# SparkFun_Thing_Plus_NORA_W306.net
KiCad netlist of a schematic drawn in EAGLE
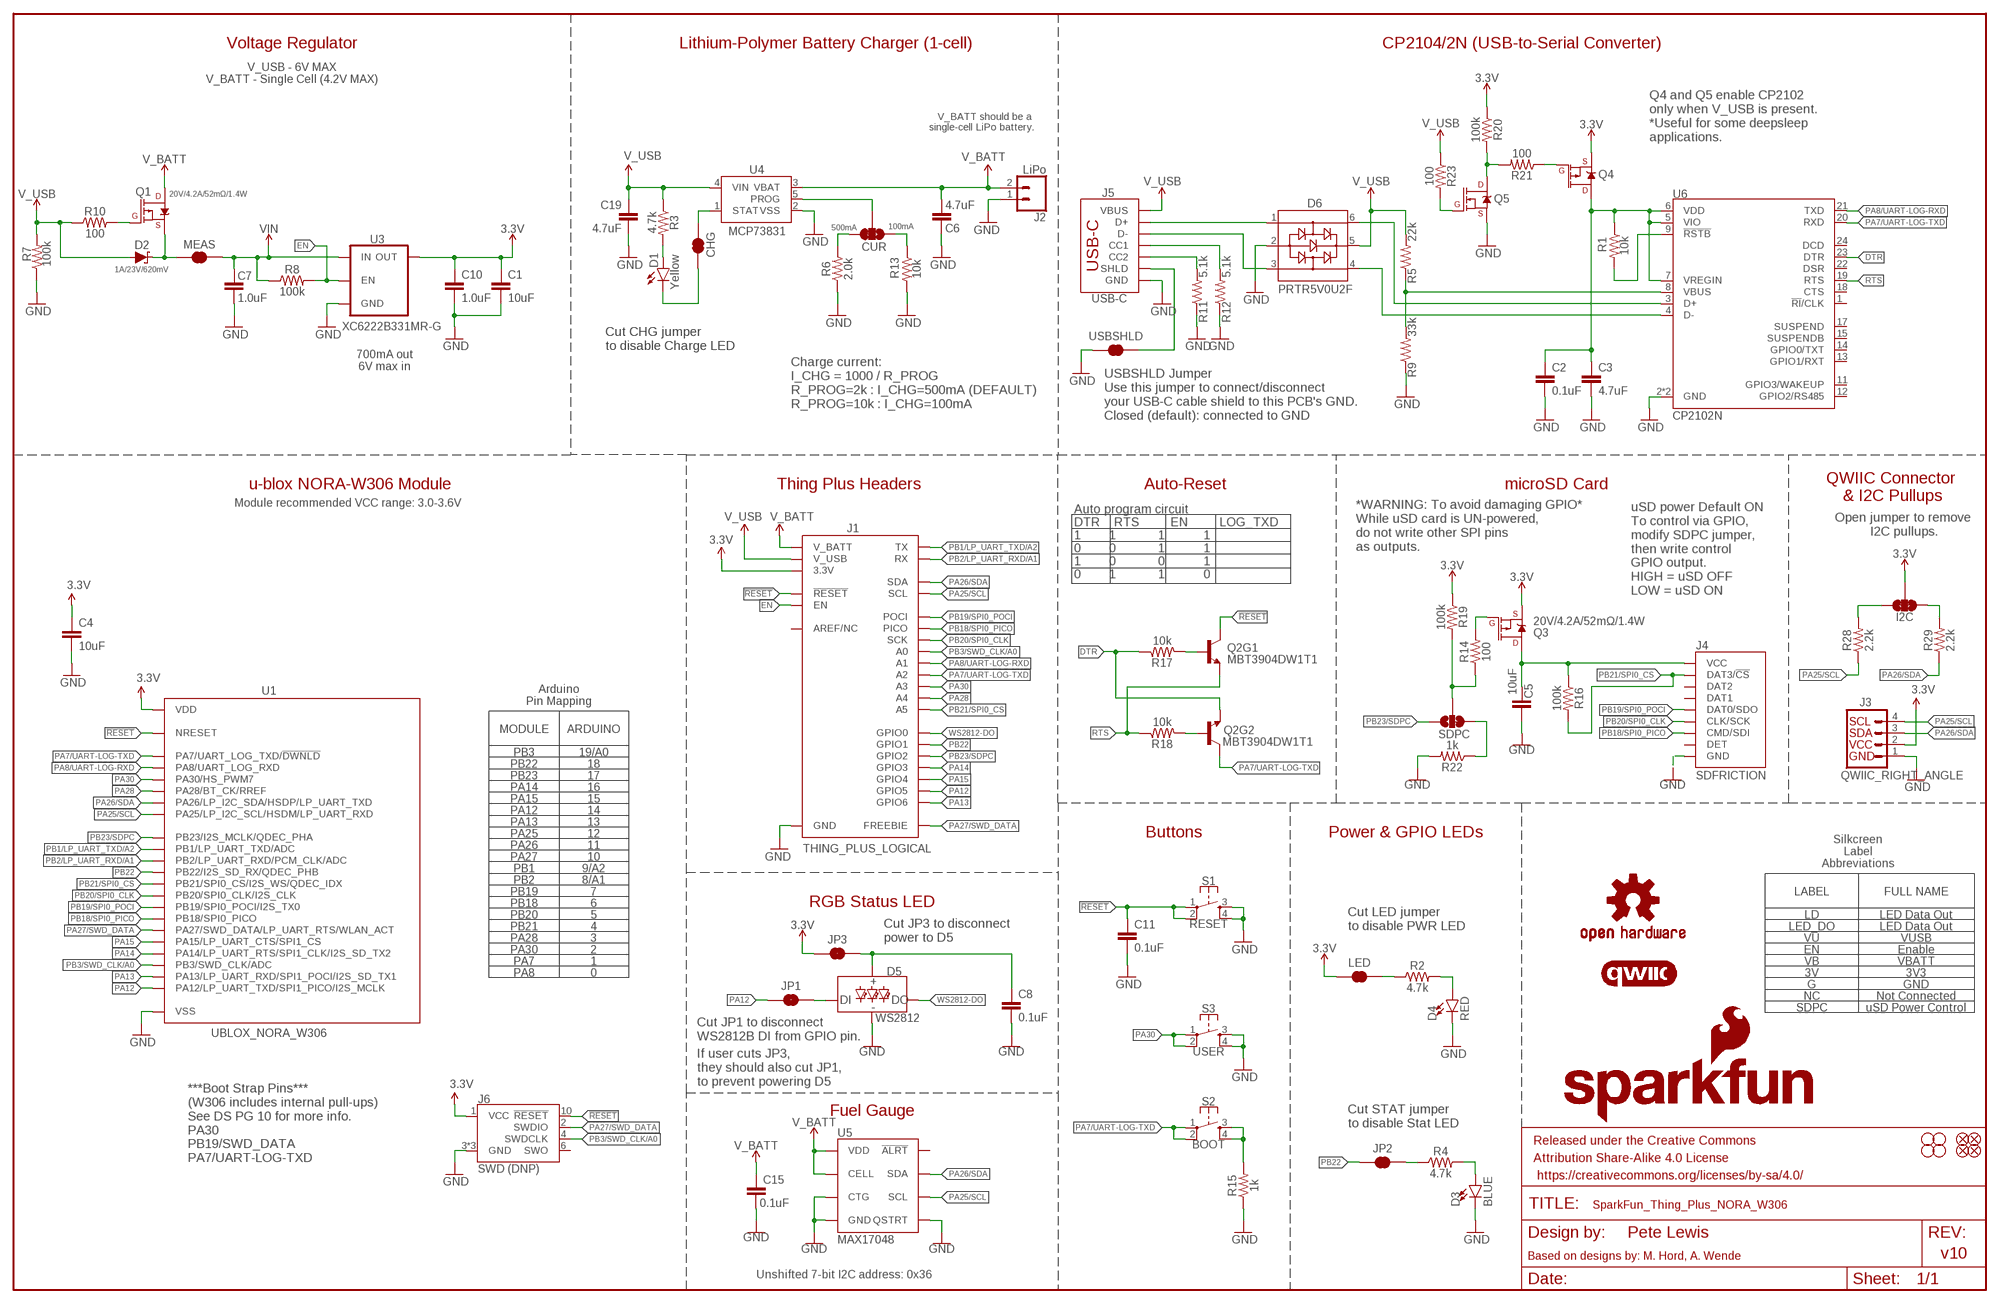
[diagram p0: schematic, sheet 1]

(export (version "E")
  (design (tool "Eeschema 10.0.6"))
  (components
    (comp (ref "C1")
      (value "10uF")
      (footprint "eagle-import:0402-TIGHT")
      (libsource (lib "eagle-import") (part "10UF-0402T-6.3V-20%"))
    )
    (comp (ref "C2")
      (value "0.1uF")
      (footprint "eagle-import:0402-TIGHT")
      (libsource (lib "eagle-import") (part "0.1UF-0402T-16V-10%"))
    )
    (comp (ref "C3")
      (value "4.7uF")
      (footprint "eagle-import:0603")
      (libsource (lib "eagle-import") (part "4.7UF-0603-35V-(20%)"))
    )
    (comp (ref "C4")
      (value "10uF")
      (footprint "eagle-import:0402-TIGHT")
      (libsource (lib "eagle-import") (part "10UF-0402T-6.3V-20%"))
    )
    (comp (ref "C5")
      (value "10uF")
      (footprint "eagle-import:0402-TIGHT")
      (libsource (lib "eagle-import") (part "10UF-0402T-6.3V-20%"))
    )
    (comp (ref "C6")
      (value "4.7uF")
      (footprint "eagle-import:0603")
      (libsource (lib "eagle-import") (part "4.7UF-0603-35V-(20%)"))
    )
    (comp (ref "C7")
      (value "1.0uF")
      (footprint "eagle-import:0402-TIGHT")
      (libsource (lib "eagle-import") (part "1.0UF-0402T-16V-10%"))
    )
    (comp (ref "C8")
      (value "0.1uF")
      (footprint "eagle-import:0402-TIGHT")
      (libsource (lib "eagle-import") (part "0.1UF-0402T-16V-10%"))
    )
    (comp (ref "C10")
      (value "1.0uF")
      (footprint "eagle-import:0402-TIGHT")
      (libsource (lib "eagle-import") (part "1.0UF-0402T-16V-10%"))
    )
    (comp (ref "C11")
      (value "0.1uF")
      (footprint "eagle-import:0402-TIGHT")
      (libsource (lib "eagle-import") (part "0.1UF-0402T-16V-10%"))
    )
    (comp (ref "C15")
      (value "0.1uF")
      (footprint "eagle-import:0402-TIGHT")
      (libsource (lib "eagle-import") (part "0.1UF-0402T-16V-10%"))
    )
    (comp (ref "C19")
      (value "4.7uF")
      (footprint "eagle-import:0603")
      (libsource (lib "eagle-import") (part "4.7UF-0603-35V-(20%)"))
    )
    (comp (ref "CHG")
      (value "JUMPER-SMT_2_NC_TRACE_SILK")
      (footprint "eagle-import:SMT-JUMPER_2_NC_TRACE_SILK")
      (libsource (lib "eagle-import") (part "JUMPER-SMT_2_NC_TRACE_SILK"))
    )
    (comp (ref "CUR")
      (value "JUMPER-SMT_3_1-NC_TRACE_SILK")
      (footprint "eagle-import:SMT-JUMPER_3_1-NC_TRACE_SILK")
      (libsource (lib "eagle-import") (part "JUMPER-SMT_3_1-NC_TRACE_SILK"))
    )
    (comp (ref "D1")
      (value "Yellow")
      (footprint "eagle-import:LED-0603")
      (libsource (lib "eagle-import") (part "LED-YELLOW0603"))
    )
    (comp (ref "D2")
      (value "1A/23V/620mV")
      (footprint "eagle-import:SOD-323")
      (libsource (lib "eagle-import") (part "DIODE-SCHOTTKY-BAT20J"))
    )
    (comp (ref "D3")
      (value "BLUE")
      (footprint "eagle-import:LED-0603")
      (libsource (lib "eagle-import") (part "LED-BLUE0603"))
    )
    (comp (ref "D4")
      (value "RED")
      (footprint "eagle-import:LED-0603")
      (libsource (lib "eagle-import") (part "LED-RED_0603-KB"))
    )
    (comp (ref "D5")
      (value "WS2812")
      (footprint "eagle-import:WS2812-2020")
      (libsource (lib "eagle-import") (part "WS2812_2020"))
    )
    (comp (ref "D6")
      (value "PRTR5V0U2F")
      (footprint "eagle-import:SOT886")
      (libsource (lib "eagle-import") (part "PRTR5V0U2F"))
    )
    (comp (ref "FD1")
      (value "FIDUCIALUFIDUCIAL")
      (footprint "eagle-import:FIDUCIAL-MICRO")
      (libsource (lib "eagle-import") (part "FIDUCIALUFIDUCIAL"))
    )
    (comp (ref "FD2")
      (value "FIDUCIALUFIDUCIAL")
      (footprint "eagle-import:FIDUCIAL-MICRO")
      (libsource (lib "eagle-import") (part "FIDUCIALUFIDUCIAL"))
    )
    (comp (ref "FD3")
      (value "FIDUCIALUFIDUCIAL")
      (footprint "eagle-import:FIDUCIAL-MICRO")
      (libsource (lib "eagle-import") (part "FIDUCIALUFIDUCIAL"))
    )
    (comp (ref "FD4")
      (value "FIDUCIALUFIDUCIAL")
      (footprint "eagle-import:FIDUCIAL-MICRO")
      (libsource (lib "eagle-import") (part "FIDUCIALUFIDUCIAL"))
    )
    (comp (ref "FRAME1")
      (value "FRAME-LEDGER")
      (footprint "eagle-import:CREATIVE_COMMONS")
      (libsource (lib "eagle-import") (part "FRAME-LEDGER"))
    )
    (comp (ref "H1")
      (value "STAND-OFF")
      (footprint "eagle-import:STAND-OFF")
      (libsource (lib "eagle-import") (part "STAND-OFF"))
    )
    (comp (ref "H2")
      (value "STAND-OFF")
      (footprint "eagle-import:STAND-OFF")
      (libsource (lib "eagle-import") (part "STAND-OFF"))
    )
    (comp (ref "H3")
      (value "STAND-OFF")
      (footprint "eagle-import:STAND-OFF")
      (libsource (lib "eagle-import") (part "STAND-OFF"))
    )
    (comp (ref "H4")
      (value "STAND-OFF")
      (footprint "eagle-import:STAND-OFF")
      (libsource (lib "eagle-import") (part "STAND-OFF"))
    )
    (comp (ref "I2C")
      (value "JUMPER-SMT_3_2-NC_TRACE_SILK")
      (footprint "eagle-import:SMT-JUMPER_3_2-NC_TRACE_SILK")
      (libsource (lib "eagle-import") (part "JUMPER-SMT_3_2-NC_TRACE_SILK"))
    )
    (comp (ref "J1")
      (value "THING_PLUS_LOGICAL")
      (footprint "eagle-import:THING_PLUS")
      (libsource (lib "eagle-import") (part "THING_PLUS_LOGICAL"))
    )
    (comp (ref "J2")
      (value "LiPo")
      (footprint "eagle-import:JST-2-SMD")
      (libsource (lib "eagle-import") (part "CONN_02-JST-2MM-SMT"))
    )
    (comp (ref "J3")
      (value "QWIIC_RIGHT_ANGLE")
      (footprint "eagle-import:JST04_1MM_RA")
      (libsource (lib "eagle-import") (part "QWIIC_CONNECTORJS-1MM"))
    )
    (comp (ref "J4")
      (value "SDFRICTION")
      (footprint "eagle-import:MICROSD_TINY")
      (libsource (lib "eagle-import") (part "MICRO-SDFRICTION"))
    )
    (comp (ref "J5")
      (value "USB-C")
      (footprint "eagle-import:USB-C-16P-4LAYER-ISOLATED")
      (libsource (lib "eagle-import") (part "USB_C_4-LAYER-ISOLATED"))
    )
    (comp (ref "J6")
      (value "SWD (DNP)")
      (footprint "eagle-import:2X5-SMD-UNSHROUDED_DNP_NO_PASTE")
      (libsource (lib "eagle-import") (part "CORTEX_JTAG_DEBUG_MINIMUM_SMD_UNSHROUDED_DNP_NO_PASTE"))
    )
    (comp (ref "JP1")
      (value "JUMPER-SMT_2_NC_TRACE_SILK")
      (footprint "eagle-import:SMT-JUMPER_2_NC_TRACE_SILK")
      (libsource (lib "eagle-import") (part "JUMPER-SMT_2_NC_TRACE_SILK"))
    )
    (comp (ref "JP2")
      (value "JUMPER-SMT_2_NC_TRACE_SILK")
      (footprint "eagle-import:SMT-JUMPER_2_NC_TRACE_SILK")
      (libsource (lib "eagle-import") (part "JUMPER-SMT_2_NC_TRACE_SILK"))
    )
    (comp (ref "JP3")
      (value "JUMPER-SMT_2_NC_TRACE_SILK")
      (footprint "eagle-import:SMT-JUMPER_2_NC_TRACE_SILK")
      (libsource (lib "eagle-import") (part "JUMPER-SMT_2_NC_TRACE_SILK"))
    )
    (comp (ref "LED")
      (value "JUMPER-SMT_2_NC_TRACE_SILK")
      (footprint "eagle-import:SMT-JUMPER_2_NC_TRACE_SILK")
      (libsource (lib "eagle-import") (part "JUMPER-SMT_2_NC_TRACE_SILK"))
    )
    (comp (ref "LOGO2")
      (value "OSHW-LOGOM")
      (footprint "eagle-import:OSHW-LOGO-M")
      (libsource (lib "eagle-import") (part "OSHW-LOGOM"))
    )
    (comp (ref "LOGO3")
      (value "SFE_LOGO_NAME_FLAME.1_INCH")
      (footprint "eagle-import:SFE_LOGO_NAME_FLAME_.1")
      (libsource (lib "eagle-import") (part "SFE_LOGO_NAME_FLAME.1_INCH"))
    )
    (comp (ref "LOGO6")
      (value "QWIIC_LOGO_4MM")
      (footprint "eagle-import:QWIIC_4MM")
      (libsource (lib "eagle-import") (part "QWIIC_LOGO_4MM"))
    )
    (comp (ref "MEAS")
      (value "JUMPER-COMBO_2_NC_TRACE")
      (footprint "eagle-import:COMBO-JUMPER_2_NC_TRACE")
      (libsource (lib "eagle-import") (part "JUMPER-COMBO_2_NC_TRACE"))
    )
    (comp (ref "Q1")
      (value "20V/4.2A/52mΩ/1.4W")
      (footprint "eagle-import:SOT23-3")
      (libsource (lib "eagle-import") (part "MOSFET_PCH-DMG2305UX-7"))
    )
    (comp (ref "Q2")
      (value "MBT3904DW1T1")
      (footprint "eagle-import:SC70-6")
      (libsource (lib "eagle-import") (part "TRANS_NPN_DUAL-MBT3904DW1T1"))
    )
    (comp (ref "Q3")
      (value "20V/4.2A/52mΩ/1.4W")
      (footprint "eagle-import:SOT23-3")
      (libsource (lib "eagle-import") (part "MOSFET_PCH-DMG2305UX-7"))
    )
    (comp (ref "Q4")
      (value "20V/4.2A/52mΩ/1.4W")
      (footprint "eagle-import:SOT23-3")
      (libsource (lib "eagle-import") (part "MOSFET_PCH-DMG2305UX-7"))
    )
    (comp (ref "Q5")
      (value "20V/0.2A/8MHz/1.2Ω/1Vth")
      (footprint "eagle-import:SOT-416FL")
      (libsource (lib "eagle-import") (part "MOSFET-NCH-RE1C002UNTCL"))
    )
    (comp (ref "R1")
      (value "10k")
      (footprint "eagle-import:0402-TIGHT")
      (libsource (lib "eagle-import") (part "10KOHM-0402T-1/16W-1%"))
    )
    (comp (ref "R2")
      (value "4.7k")
      (footprint "eagle-import:0402-TIGHT")
      (libsource (lib "eagle-import") (part "4.7KOHM-0402T-1/16W-1%"))
    )
    (comp (ref "R3")
      (value "4.7k")
      (footprint "eagle-import:0402-TIGHT")
      (libsource (lib "eagle-import") (part "4.7KOHM-0402T-1/16W-1%"))
    )
    (comp (ref "R4")
      (value "4.7k")
      (footprint "eagle-import:0402-TIGHT")
      (libsource (lib "eagle-import") (part "4.7KOHM-0402T-1/16W-1%"))
    )
    (comp (ref "R5")
      (value "22k")
      (footprint "eagle-import:0402-TIGHT")
      (libsource (lib "eagle-import") (part "22KOHM-0402_TIGHT-1/10W-1%"))
    )
    (comp (ref "R6")
      (value "2.0k")
      (footprint "eagle-import:0603")
      (libsource (lib "eagle-import") (part "2.0KOHM-0603-1/10W-5%"))
    )
    (comp (ref "R7")
      (value "100k")
      (footprint "eagle-import:0402-TIGHT")
      (libsource (lib "eagle-import") (part "100KOHM-0402T-1/16W-1%"))
    )
    (comp (ref "R8")
      (value "100k")
      (footprint "eagle-import:0402-TIGHT")
      (libsource (lib "eagle-import") (part "100KOHM-0402T-1/16W-1%"))
    )
    (comp (ref "R9")
      (value "33k")
      (footprint "eagle-import:0402-TIGHT")
      (libsource (lib "eagle-import") (part "33KOHM-0402T-1/16W-1%"))
    )
    (comp (ref "R10")
      (value "100")
      (footprint "eagle-import:0402-TIGHT")
      (libsource (lib "eagle-import") (part "100OHM-0402-TIGHT-1/16W-1%"))
    )
    (comp (ref "R11")
      (value "5.1k")
      (footprint "eagle-import:0402-TIGHT")
      (libsource (lib "eagle-import") (part "5.1KOHM-0402T-1/16W-1%"))
    )
    (comp (ref "R12")
      (value "5.1k")
      (footprint "eagle-import:0402-TIGHT")
      (libsource (lib "eagle-import") (part "5.1KOHM-0402T-1/16W-1%"))
    )
    (comp (ref "R13")
      (value "10k")
      (footprint "eagle-import:0402-TIGHT")
      (libsource (lib "eagle-import") (part "10KOHM-0402T-1/16W-1%"))
    )
    (comp (ref "R14")
      (value "100")
      (footprint "eagle-import:0402-TIGHT")
      (libsource (lib "eagle-import") (part "100OHM-0402-TIGHT-1/16W-1%"))
    )
    (comp (ref "R15")
      (value "1k")
      (footprint "eagle-import:0402-TIGHT")
      (libsource (lib "eagle-import") (part "1KOHM-0402T-1/16W-1%"))
    )
    (comp (ref "R16")
      (value "100k")
      (footprint "eagle-import:0402-TIGHT")
      (libsource (lib "eagle-import") (part "100KOHM-0402T-1/16W-1%"))
    )
    (comp (ref "R17")
      (value "10k")
      (footprint "eagle-import:0402-TIGHT")
      (libsource (lib "eagle-import") (part "10KOHM-0402T-1/16W-1%"))
    )
    (comp (ref "R18")
      (value "10k")
      (footprint "eagle-import:0402-TIGHT")
      (libsource (lib "eagle-import") (part "10KOHM-0402T-1/16W-1%"))
    )
    (comp (ref "R19")
      (value "100k")
      (footprint "eagle-import:0402-TIGHT")
      (libsource (lib "eagle-import") (part "100KOHM-0402T-1/16W-1%"))
    )
    (comp (ref "R20")
      (value "100k")
      (footprint "eagle-import:0402-TIGHT")
      (libsource (lib "eagle-import") (part "100KOHM-0402T-1/16W-1%"))
    )
    (comp (ref "R21")
      (value "100")
      (footprint "eagle-import:0402-TIGHT")
      (libsource (lib "eagle-import") (part "100OHM-0402-TIGHT-1/16W-1%"))
    )
    (comp (ref "R22")
      (value "1k")
      (footprint "eagle-import:0402-TIGHT")
      (libsource (lib "eagle-import") (part "1KOHM-0402T-1/16W-1%"))
    )
    (comp (ref "R23")
      (value "100")
      (footprint "eagle-import:0402-TIGHT")
      (libsource (lib "eagle-import") (part "100OHM-0402-TIGHT-1/16W-1%"))
    )
    (comp (ref "R28")
      (value "2.2k")
      (footprint "eagle-import:0402-TIGHT")
      (libsource (lib "eagle-import") (part "2.2KOHM-0402T-1/16W-1%"))
    )
    (comp (ref "R29")
      (value "2.2k")
      (footprint "eagle-import:0402-TIGHT")
      (libsource (lib "eagle-import") (part "2.2KOHM-0402T-1/16W-1%"))
    )
    (comp (ref "S1")
      (value "RESET")
      (footprint "eagle-import:TACTILE_SWITCH_SMD_4.6X2.8MM")
      (libsource (lib "eagle-import") (part "MOMENTARY-SWITCH-SPST-2-SMD-4.6X2.8MM"))
    )
    (comp (ref "S2")
      (value "BOOT")
      (footprint "eagle-import:TACTILE_SWITCH_SMD_4.6X2.8MM")
      (libsource (lib "eagle-import") (part "MOMENTARY-SWITCH-SPST-2-SMD-4.6X2.8MM"))
    )
    (comp (ref "S3")
      (value "USER")
      (footprint "eagle-import:TACTILE_SWITCH_SMD_4.6X2.8MM")
      (libsource (lib "eagle-import") (part "MOMENTARY-SWITCH-SPST-2-SMD-4.6X2.8MM"))
    )
    (comp (ref "SDPC")
      (value "JUMPER-SMT_3_1-NC_TRACE_SILK")
      (footprint "eagle-import:SMT-JUMPER_3_1-NC_TRACE_SILK")
      (libsource (lib "eagle-import") (part "JUMPER-SMT_3_1-NC_TRACE_SILK"))
    )
    (comp (ref "U1")
      (value "UBLOX_NORA_W306")
      (footprint "eagle-import:UBLOX-NORA-W3")
      (libsource (lib "eagle-import") (part "UBLOX_NORA_W306"))
    )
    (comp (ref "U3")
      (value "XC6222B331MR-G")
      (footprint "eagle-import:SOT23-5")
      (libsource (lib "eagle-import") (part "XC6222B331MR-G"))
    )
    (comp (ref "U4")
      (value "MCP73831")
      (footprint "eagle-import:SOT23-5")
      (libsource (lib "eagle-import") (part "MCP73831"))
    )
    (comp (ref "U5")
      (value "MAX17048")
      (footprint "eagle-import:DFN-8")
      (libsource (lib "eagle-import") (part "MAX17048DFN8"))
    )
    (comp (ref "U6")
      (value "CP2102N")
      (footprint "eagle-import:QFN24")
      (libsource (lib "eagle-import") (part "CP2102N"))
    )
    (comp (ref "USBSHLD")
      (value "JUMPER-SMT_2_NC_TRACE_SILK")
      (footprint "eagle-import:SMT-JUMPER_2_NC_TRACE_SILK")
      (libsource (lib "eagle-import") (part "JUMPER-SMT_2_NC_TRACE_SILK"))
    )
  )
  (nets
    (net (code "1") (name "/~{RESET}") (class "Default")
      (node (ref "C11") (pin "1") (pinfunction "1_1") (pintype "passive"))
      (node (ref "J1") (pin "28") (pinfunction "~{RESET}_28") (pintype "bidirectional"))
      (node (ref "J6") (pin "10") (pinfunction "~{RESET}_10") (pintype "bidirectional"))
      (node (ref "Q2") (pin "3") (pinfunction "C_3") (pintype "passive"))
      (node (ref "S1") (pin "1") (pinfunction "1_1") (pintype "passive"))
      (node (ref "S1") (pin "2") (pinfunction "2_2") (pintype "passive"))
      (node (ref "U1") (pin "J3") (pinfunction "NRESET_J3") (pintype "bidirectional"))
    )
    (net (code "2") (name "3.3V") (class "Default")
      (node (ref "C1") (pin "1") (pinfunction "1_1") (pintype "passive"))
      (node (ref "C10") (pin "1") (pinfunction "1_1") (pintype "passive"))
      (node (ref "C4") (pin "1") (pinfunction "1_1") (pintype "passive"))
      (node (ref "I2C") (pin "2") (pinfunction "2_2") (pintype "passive"))
      (node (ref "J1") (pin "27") (pinfunction "3.3V_27") (pintype "bidirectional"))
      (node (ref "J3") (pin "2") (pinfunction "2_2") (pintype "power_in"))
      (node (ref "J6") (pin "1") (pinfunction "VCC_1") (pintype "bidirectional"))
      (node (ref "JP3") (pin "1") (pinfunction "1_1") (pintype "passive"))
      (node (ref "LED") (pin "1") (pinfunction "1_1") (pintype "passive"))
      (node (ref "Q3") (pin "2") (pinfunction "S_2") (pintype "bidirectional"))
      (node (ref "Q4") (pin "2") (pinfunction "S_2") (pintype "bidirectional"))
      (node (ref "R19") (pin "1") (pinfunction "1_1") (pintype "passive"))
      (node (ref "R20") (pin "1") (pinfunction "1_1") (pintype "passive"))
      (node (ref "U1") (pin "A7") (pinfunction "VDD_A7") (pintype "bidirectional"))
      (node (ref "U1") (pin "A8") (pinfunction "VDD_A8") (pintype "bidirectional"))
      (node (ref "U1") (pin "B7") (pinfunction "VDD_B7") (pintype "bidirectional"))
      (node (ref "U3") (pin "5") (pinfunction "OUT_5") (pintype "passive"))
    )
    (net (code "3") (name "DTR") (class "Default")
      (node (ref "Q2") (pin "1") (pinfunction "E_1") (pintype "passive"))
      (node (ref "R17") (pin "1") (pinfunction "1_1") (pintype "passive"))
      (node (ref "U6") (pin "23") (pinfunction "DTR_23") (pintype "bidirectional"))
    )
    (net (code "4") (name "EN") (class "Default")
      (node (ref "J1") (pin "11") (pinfunction "EN_11") (pintype "bidirectional"))
      (node (ref "R8") (pin "2") (pinfunction "2_2") (pintype "passive"))
      (node (ref "U3") (pin "3") (pinfunction "EN_3") (pintype "input"))
    )
    (net (code "5") (name "GND") (class "Default")
      (node (ref "C1") (pin "2") (pinfunction "2_2") (pintype "passive"))
      (node (ref "C10") (pin "2") (pinfunction "2_2") (pintype "passive"))
      (node (ref "C11") (pin "2") (pinfunction "2_2") (pintype "passive"))
      (node (ref "C15") (pin "2") (pinfunction "2_2") (pintype "passive"))
      (node (ref "C19") (pin "2") (pinfunction "2_2") (pintype "passive"))
      (node (ref "C2") (pin "2") (pinfunction "2_2") (pintype "passive"))
      (node (ref "C3") (pin "2") (pinfunction "2_2") (pintype "passive"))
      (node (ref "C4") (pin "2") (pinfunction "2_2") (pintype "passive"))
      (node (ref "C5") (pin "2") (pinfunction "2_2") (pintype "passive"))
      (node (ref "C6") (pin "2") (pinfunction "2_2") (pintype "passive"))
      (node (ref "C7") (pin "2") (pinfunction "2_2") (pintype "passive"))
      (node (ref "C8") (pin "2") (pinfunction "2_2") (pintype "passive"))
      (node (ref "D3") (pin "C") (pinfunction "C_C") (pintype "passive"))
      (node (ref "D4") (pin "C") (pinfunction "C_C") (pintype "passive"))
      (node (ref "D5") (pin "GND") (pinfunction "GND_GND") (pintype "bidirectional"))
      (node (ref "D6") (pin "2") (pinfunction "2_2") (pintype "power_in"))
      (node (ref "J1") (pin "25") (pinfunction "GND_25") (pintype "bidirectional"))
      (node (ref "J2") (pin "1") (pinfunction "2_1") (pintype "passive"))
      (node (ref "J3") (pin "1") (pinfunction "1_1") (pintype "power_in"))
      (node (ref "J4") (pin "6") (pinfunction "GND_6") (pintype "bidirectional"))
      (node (ref "J4") (pin "GND1") (pinfunction "GND_GND1") (pintype "bidirectional"))
      (node (ref "J4") (pin "GND2") (pinfunction "GND_GND2") (pintype "bidirectional"))
      (node (ref "J4") (pin "GND3") (pinfunction "GND_GND3") (pintype "bidirectional"))
      (node (ref "J4") (pin "GND4") (pinfunction "GND_GND4") (pintype "bidirectional"))
      (node (ref "J4") (pin "GND5") (pinfunction "GND_GND5") (pintype "bidirectional"))
      (node (ref "J4") (pin "GND6") (pinfunction "GND_GND6") (pintype "bidirectional"))
      (node (ref "J5") (pin "GND") (pinfunction "GND_GND") (pintype "bidirectional"))
      (node (ref "J5") (pin "GND2") (pinfunction "GND_GND2") (pintype "bidirectional"))
      (node (ref "J6") (pin "3") (pinfunction "GND_3") (pintype "bidirectional"))
      (node (ref "J6") (pin "5") (pinfunction "GND_5") (pintype "bidirectional"))
      (node (ref "J6") (pin "9") (pinfunction "GND_9") (pintype "bidirectional"))
      (node (ref "Q5") (pin "2") (pinfunction "S_2") (pintype "bidirectional"))
      (node (ref "R11") (pin "1") (pinfunction "1_1") (pintype "passive"))
      (node (ref "R12") (pin "1") (pinfunction "1_1") (pintype "passive"))
      (node (ref "R13") (pin "2") (pinfunction "2_2") (pintype "passive"))
      (node (ref "R15") (pin "1") (pinfunction "1_1") (pintype "passive"))
      (node (ref "R22") (pin "2") (pinfunction "2_2") (pintype "passive"))
      (node (ref "R6") (pin "1") (pinfunction "1_1") (pintype "passive"))
      (node (ref "R7") (pin "1") (pinfunction "1_1") (pintype "passive"))
      (node (ref "R9") (pin "1") (pinfunction "1_1") (pintype "passive"))
      (node (ref "S1") (pin "3") (pinfunction "3_3") (pintype "passive"))
      (node (ref "S1") (pin "4") (pinfunction "4_4") (pintype "passive"))
      (node (ref "S3") (pin "3") (pinfunction "3_3") (pintype "passive"))
      (node (ref "S3") (pin "4") (pinfunction "4_4") (pintype "passive"))
      (node (ref "U1") (pin "A1") (pinfunction "VSS_A1") (pintype "bidirectional"))
      (node (ref "U1") (pin "A9") (pinfunction "VSS_A9") (pintype "bidirectional"))
      (node (ref "U1") (pin "B2") (pinfunction "VSS_B2") (pintype "bidirectional"))
      (node (ref "U1") (pin "B8") (pinfunction "VSS_B8") (pintype "bidirectional"))
      (node (ref "U1") (pin "E4") (pinfunction "VSS_E4") (pintype "bidirectional"))
      (node (ref "U1") (pin "E5") (pinfunction "VSS_E5") (pintype "bidirectional"))
      (node (ref "U1") (pin "F4") (pinfunction "VSS_F4") (pintype "bidirectional"))
      (node (ref "U1") (pin "F5") (pinfunction "VSS_F5") (pintype "bidirectional"))
      (node (ref "U1") (pin "K2") (pinfunction "VSS_K2") (pintype "bidirectional"))
      (node (ref "U1") (pin "K3") (pinfunction "VSS_K3") (pintype "bidirectional"))
      (node (ref "U1") (pin "K5") (pinfunction "VSS_K5") (pintype "bidirectional"))
      (node (ref "U1") (pin "K7") (pinfunction "VSS_K7") (pintype "bidirectional"))
      (node (ref "U1") (pin "K8") (pinfunction "VSS_K8") (pintype "bidirectional"))
      (node (ref "U1") (pin "L1") (pinfunction "VSS_L1") (pintype "bidirectional"))
      (node (ref "U1") (pin "L9") (pinfunction "VSS_L9") (pintype "bidirectional"))
      (node (ref "U1") (pin "M1") (pinfunction "VSS_M1") (pintype "bidirectional"))
      (node (ref "U1") (pin "M2") (pinfunction "VSS_M2") (pintype "bidirectional"))
      (node (ref "U1") (pin "M8") (pinfunction "VSS_M8") (pintype "bidirectional"))
      (node (ref "U1") (pin "M9") (pinfunction "VSS_M9") (pintype "bidirectional"))
      (node (ref "U3") (pin "2") (pinfunction "GND_2") (pintype "input"))
      (node (ref "U4") (pin "2") (pinfunction "VSS_2") (pintype "power_in"))
      (node (ref "U5") (pin "1") (pinfunction "CTG_1") (pintype "input"))
      (node (ref "U5") (pin "4") (pinfunction "GND_4") (pintype "bidirectional"))
      (node (ref "U5") (pin "6") (pinfunction "QSTRT_6") (pintype "bidirectional"))
      (node (ref "U5") (pin "9") (pinfunction "GND_9") (pintype "bidirectional"))
      (node (ref "U6") (pin "2") (pinfunction "GND_2") (pintype "bidirectional"))
      (node (ref "U6") (pin "PAD") (pinfunction "GND_PAD") (pintype "bidirectional"))
      (node (ref "USBSHLD") (pin "1") (pinfunction "1_1") (pintype "passive"))
    )
    (net (code "6") (name "Net-(C8-Pad1)") (class "Default")
      (node (ref "C8") (pin "1") (pinfunction "1_1") (pintype "passive"))
      (node (ref "D5") (pin "VCC") (pinfunction "VCC_VCC") (pintype "bidirectional"))
      (node (ref "JP3") (pin "2") (pinfunction "2_2") (pintype "passive"))
    )
    (net (code "7") (name "Net-(CHG-Pad1)") (class "Default")
      (node (ref "CHG") (pin "1") (pinfunction "1_1") (pintype "passive"))
      (node (ref "D1") (pin "C") (pinfunction "C_C") (pintype "passive"))
    )
    (net (code "8") (name "Net-(CUR-Pad1)") (class "Default")
      (node (ref "CUR") (pin "1") (pinfunction "1_1") (pintype "passive"))
      (node (ref "R13") (pin "1") (pinfunction "1_1") (pintype "passive"))
    )
    (net (code "9") (name "Net-(CUR-Pad3)") (class "Default")
      (node (ref "CUR") (pin "3") (pinfunction "3_3") (pintype "passive"))
      (node (ref "R6") (pin "2") (pinfunction "2_2") (pintype "passive"))
    )
    (net (code "10") (name "Net-(D1-PadA)") (class "Default")
      (node (ref "D1") (pin "A") (pinfunction "A_A") (pintype "passive"))
      (node (ref "R3") (pin "2") (pinfunction "2_2") (pintype "passive"))
    )
    (net (code "11") (name "Net-(D3-PadA)") (class "Default")
      (node (ref "D3") (pin "A") (pinfunction "A_A") (pintype "passive"))
      (node (ref "R4") (pin "2") (pinfunction "2_2") (pintype "passive"))
    )
    (net (code "12") (name "Net-(D4-PadA)") (class "Default")
      (node (ref "D4") (pin "A") (pinfunction "A_A") (pintype "passive"))
      (node (ref "R2") (pin "2") (pinfunction "2_2") (pintype "passive"))
    )
    (net (code "13") (name "Net-(D5-PadDI)") (class "Default")
      (node (ref "D5") (pin "DI") (pinfunction "DI_DI") (pintype "bidirectional"))
      (node (ref "JP1") (pin "2") (pinfunction "2_2") (pintype "passive"))
    )
    (net (code "14") (name "Net-(D6-Pad1)") (class "Default")
      (node (ref "D6") (pin "1") (pinfunction "1_1") (pintype "bidirectional"))
      (node (ref "J5") (pin "A6") (pinfunction "D+_A6") (pintype "bidirectional"))
      (node (ref "J5") (pin "B6") (pinfunction "D+_B6") (pintype "bidirectional"))
    )
    (net (code "15") (name "Net-(D6-Pad3)") (class "Default")
      (node (ref "D6") (pin "3") (pinfunction "3_3") (pintype "bidirectional"))
      (node (ref "J5") (pin "A7") (pinfunction "D-_A7") (pintype "bidirectional"))
      (node (ref "J5") (pin "B7") (pinfunction "D-_B7") (pintype "bidirectional"))
    )
    (net (code "16") (name "Net-(I2C-Pad1)") (class "Default")
      (node (ref "I2C") (pin "1") (pinfunction "1_1") (pintype "passive"))
      (node (ref "R29") (pin "2") (pinfunction "2_2") (pintype "passive"))
    )
    (net (code "17") (name "Net-(I2C-Pad3)") (class "Default")
      (node (ref "I2C") (pin "3") (pinfunction "3_3") (pintype "passive"))
      (node (ref "R28") (pin "2") (pinfunction "2_2") (pintype "passive"))
    )
    (net (code "18") (name "Net-(J4-VCC)") (class "Default")
      (node (ref "C5") (pin "1") (pinfunction "1_1") (pintype "passive"))
      (node (ref "J4") (pin "4") (pinfunction "VCC_4") (pintype "bidirectional"))
      (node (ref "Q3") (pin "3") (pinfunction "D_3") (pintype "bidirectional"))
      (node (ref "R16") (pin "1") (pinfunction "1_1") (pintype "passive"))
    )
    (net (code "19") (name "Net-(J5-CC1)") (class "Default")
      (node (ref "J5") (pin "A5") (pinfunction "CC1_A5") (pintype "bidirectional"))
      (node (ref "R12") (pin "2") (pinfunction "2_2") (pintype "passive"))
    )
    (net (code "20") (name "Net-(J5-CC2)") (class "Default")
      (node (ref "J5") (pin "B5") (pinfunction "CC2_B5") (pintype "bidirectional"))
      (node (ref "R11") (pin "2") (pinfunction "2_2") (pintype "passive"))
    )
    (net (code "21") (name "Net-(J5-SHLD-PadSHLD1)") (class "Default")
      (node (ref "J5") (pin "SHLD1") (pinfunction "SHLD_SHLD1") (pintype "bidirectional"))
      (node (ref "J5") (pin "SHLD2") (pinfunction "SHLD_SHLD2") (pintype "bidirectional"))
      (node (ref "J5") (pin "SHLD3") (pinfunction "SHLD_SHLD3") (pintype "bidirectional"))
      (node (ref "J5") (pin "SHLD4") (pinfunction "SHLD_SHLD4") (pintype "bidirectional"))
      (node (ref "J5") (pin "SHLD5") (pinfunction "SHLD_SHLD5") (pintype "bidirectional"))
      (node (ref "J5") (pin "SHLD6") (pinfunction "SHLD_SHLD6") (pintype "bidirectional"))
      (node (ref "J5") (pin "SHLD7") (pinfunction "SHLD_SHLD7") (pintype "bidirectional"))
      (node (ref "J5") (pin "SHLD8") (pinfunction "SHLD_SHLD8") (pintype "bidirectional"))
      (node (ref "USBSHLD") (pin "2") (pinfunction "2_2") (pintype "passive"))
    )
    (net (code "22") (name "Net-(JP2-Pad2)") (class "Default")
      (node (ref "JP2") (pin "2") (pinfunction "2_2") (pintype "passive"))
      (node (ref "R4") (pin "1") (pinfunction "1_1") (pintype "passive"))
    )
    (net (code "23") (name "Net-(LED-Pad2)") (class "Default")
      (node (ref "LED") (pin "2") (pinfunction "2_2") (pintype "passive"))
      (node (ref "R2") (pin "1") (pinfunction "1_1") (pintype "passive"))
    )
    (net (code "24") (name "Net-(Q1-G)") (class "Default")
      (node (ref "Q1") (pin "1") (pinfunction "G_1") (pintype "bidirectional"))
      (node (ref "R10") (pin "2") (pinfunction "2_2") (pintype "passive"))
    )
    (net (code "25") (name "Net-(Q1-S)") (class "Default")
      (node (ref "D2") (pin "C") (pinfunction "C_C") (pintype "passive"))
      (node (ref "MEAS") (pin "1") (pinfunction "1_1") (pintype "passive"))
      (node (ref "MEAS") (pin "3") (pinfunction "1_3") (pintype "passive"))
      (node (ref "Q1") (pin "2") (pinfunction "S_2") (pintype "bidirectional"))
    )
    (net (code "26") (name "Net-(Q2A-B)") (class "Default")
      (node (ref "Q2") (pin "5") (pinfunction "B_5") (pintype "passive"))
      (node (ref "R17") (pin "2") (pinfunction "2_2") (pintype "passive"))
    )
    (net (code "27") (name "Net-(Q2B-B)") (class "Default")
      (node (ref "Q2") (pin "2") (pinfunction "B_2") (pintype "passive"))
      (node (ref "R18") (pin "2") (pinfunction "2_2") (pintype "passive"))
    )
    (net (code "28") (name "Net-(Q3-G)") (class "Default")
      (node (ref "Q3") (pin "1") (pinfunction "G_1") (pintype "bidirectional"))
      (node (ref "R14") (pin "2") (pinfunction "2_2") (pintype "passive"))
    )
    (net (code "29") (name "Net-(Q4-D)") (class "Default")
      (node (ref "C2") (pin "1") (pinfunction "1_1") (pintype "passive"))
      (node (ref "C3") (pin "1") (pinfunction "1_1") (pintype "passive"))
      (node (ref "Q4") (pin "3") (pinfunction "D_3") (pintype "bidirectional"))
      (node (ref "R1") (pin "1") (pinfunction "1_1") (pintype "passive"))
      (node (ref "U6") (pin "5") (pinfunction "VIO_5") (pintype "bidirectional"))
      (node (ref "U6") (pin "6") (pinfunction "VDD_6") (pintype "bidirectional"))
      (node (ref "U6") (pin "7") (pinfunction "VREGIN_7") (pintype "bidirectional"))
    )
    (net (code "30") (name "Net-(Q4-G)") (class "Default")
      (node (ref "Q4") (pin "1") (pinfunction "G_1") (pintype "bidirectional"))
      (node (ref "R21") (pin "1") (pinfunction "1_1") (pintype "passive"))
    )
    (net (code "31") (name "Net-(Q5-D)") (class "Default")
      (node (ref "Q5") (pin "3") (pinfunction "D_3") (pintype "bidirectional"))
      (node (ref "R20") (pin "2") (pinfunction "2_2") (pintype "passive"))
      (node (ref "R21") (pin "2") (pinfunction "2_2") (pintype "passive"))
    )
    (net (code "32") (name "Net-(Q5-G)") (class "Default")
      (node (ref "Q5") (pin "1") (pinfunction "G_1") (pintype "bidirectional"))
      (node (ref "R23") (pin "2") (pinfunction "2_2") (pintype "passive"))
    )
    (net (code "33") (name "Net-(R14-Pad1)") (class "Default")
      (node (ref "R14") (pin "1") (pinfunction "1_1") (pintype "passive"))
      (node (ref "R19") (pin "2") (pinfunction "2_2") (pintype "passive"))
      (node (ref "SDPC") (pin "2") (pinfunction "2_2") (pintype "passive"))
    )
    (net (code "34") (name "Net-(R15-Pad2)") (class "Default")
      (node (ref "R15") (pin "2") (pinfunction "2_2") (pintype "passive"))
      (node (ref "S2") (pin "3") (pinfunction "3_3") (pintype "passive"))
      (node (ref "S2") (pin "4") (pinfunction "4_4") (pintype "passive"))
    )
    (net (code "35") (name "Net-(R22-Pad1)") (class "Default")
      (node (ref "R22") (pin "1") (pinfunction "1_1") (pintype "passive"))
      (node (ref "SDPC") (pin "3") (pinfunction "3_3") (pintype "passive"))
    )
    (net (code "36") (name "Net-(U4-PROG)") (class "Default")
      (node (ref "CUR") (pin "2") (pinfunction "2_2") (pintype "passive"))
      (node (ref "U4") (pin "5") (pinfunction "PROG_5") (pintype "input"))
    )
    (net (code "37") (name "Net-(U4-STAT)") (class "Default")
      (node (ref "CHG") (pin "2") (pinfunction "2_2") (pintype "passive"))
      (node (ref "U4") (pin "1") (pinfunction "STAT_1") (pintype "output"))
    )
    (net (code "38") (name "Net-(U6-D+)") (class "Default")
      (node (ref "D6") (pin "6") (pinfunction "6_6") (pintype "bidirectional"))
      (node (ref "U6") (pin "3") (pinfunction "D+_3") (pintype "bidirectional"))
    )
    (net (code "39") (name "Net-(U6-D-)") (class "Default")
      (node (ref "D6") (pin "4") (pinfunction "4_4") (pintype "bidirectional"))
      (node (ref "U6") (pin "4") (pinfunction "D-_4") (pintype "bidirectional"))
    )
    (net (code "40") (name "Net-(U6-VBUS)") (class "Default")
      (node (ref "R5") (pin "1") (pinfunction "1_1") (pintype "passive"))
      (node (ref "R9") (pin "2") (pinfunction "2_2") (pintype "passive"))
      (node (ref "U6") (pin "8") (pinfunction "VBUS_8") (pintype "bidirectional"))
    )
    (net (code "41") (name "Net-(U6-~{RSTB})") (class "Default")
      (node (ref "R1") (pin "2") (pinfunction "2_2") (pintype "passive"))
      (node (ref "U6") (pin "9") (pinfunction "~{RSTB}_9") (pintype "bidirectional"))
    )
    (net (code "42") (name "PA7{slash}UART-LOG-TXD") (class "Default")
      (node (ref "J1") (pin "22") (pinfunction "A2_22") (pintype "bidirectional"))
      (node (ref "Q2") (pin "6") (pinfunction "C_6") (pintype "passive"))
      (node (ref "S2") (pin "1") (pinfunction "1_1") (pintype "passive"))
      (node (ref "S2") (pin "2") (pinfunction "2_2") (pintype "passive"))
      (node (ref "U1") (pin "A5") (pinfunction "PA7/UART_LOG_TXD/~{DWNLD}_A5") (pintype "bidirectional"))
      (node (ref "U6") (pin "20") (pinfunction "RXD_20") (pintype "bidirectional"))
    )
    (net (code "43") (name "PA8{slash}UART-LOG-RXD") (class "Default")
      (node (ref "J1") (pin "23") (pinfunction "A1_23") (pintype "bidirectional"))
      (node (ref "U1") (pin "A6") (pinfunction "PA8/UART_LOG_RXD_A6") (pintype "bidirectional"))
      (node (ref "U6") (pin "21") (pinfunction "TXD_21") (pintype "bidirectional"))
    )
    (net (code "44") (name "PA12") (class "Default")
      (node (ref "J1") (pin "4") (pinfunction "GPIO5_4") (pintype "bidirectional"))
      (node (ref "JP1") (pin "1") (pinfunction "1_1") (pintype "passive"))
      (node (ref "U1") (pin "J9") (pinfunction "PA12/LP_UART_TXD/SPI1_PICO/I2S_MCLK_J9") (pintype "bidirectional"))
    )
    (net (code "45") (name "PA13") (class "Default")
      (node (ref "J1") (pin "3") (pinfunction "GPIO6_3") (pintype "bidirectional"))
      (node (ref "U1") (pin "J8") (pinfunction "PA13/LP_UART_RXD/SPI1_POCI/I2S_SD_TX1_J8") (pintype "bidirectional"))
    )
    (net (code "46") (name "PA14") (class "Default")
      (node (ref "J1") (pin "6") (pinfunction "GPIO3_6") (pintype "bidirectional"))
      (node (ref "U1") (pin "H9") (pinfunction "PA14/LP_UART_RTS/SPI1_CLK/I2S_SD_TX2_H9") (pintype "bidirectional"))
    )
    (net (code "47") (name "PA15") (class "Default")
      (node (ref "J1") (pin "5") (pinfunction "GPIO4_5") (pintype "bidirectional"))
      (node (ref "U1") (pin "H8") (pinfunction "PA15/LP_UART_CTS/SPI1_CS_H8") (pintype "bidirectional"))
    )
    (net (code "48") (name "PA25{slash}SCL") (class "Default")
      (node (ref "J1") (pin "2") (pinfunction "SCL_2") (pintype "bidirectional"))
      (node (ref "J3") (pin "4") (pinfunction "4_4") (pintype "passive"))
      (node (ref "R28") (pin "1") (pinfunction "1_1") (pintype "passive"))
      (node (ref "U1") (pin "C2") (pinfunction "PA25/LP_I2C_SCL/HSDM/LP_UART_RXD_C2") (pintype "bidirectional"))
      (node (ref "U5") (pin "7") (pinfunction "SCL_7") (pintype "output"))
    )
    (net (code "49") (name "PA26{slash}SDA") (class "Default")
      (node (ref "J1") (pin "1") (pinfunction "SDA_1") (pintype "bidirectional"))
      (node (ref "J3") (pin "3") (pinfunction "3_3") (pintype "passive"))
      (node (ref "R29") (pin "1") (pinfunction "1_1") (pintype "passive"))
      (node (ref "U1") (pin "C1") (pinfunction "PA26/LP_I2C_SDA/HSDP/LP_UART_TXD_C1") (pintype "bidirectional"))
      (node (ref "U5") (pin "8") (pinfunction "SDA_8") (pintype "input"))
    )
    (net (code "50") (name "PA27{slash}SWD_DATA") (class "Default")
      (node (ref "J1") (pin "13") (pinfunction "FREEBIE_13") (pintype "bidirectional"))
      (node (ref "J6") (pin "2") (pinfunction "SWDIO_2") (pintype "bidirectional"))
      (node (ref "U1") (pin "H2") (pinfunction "PA27/SWD_DATA/LP_UART_RTS/WLAN_ACT_H2") (pintype "bidirectional"))
    )
    (net (code "51") (name "PA28") (class "Default")
      (node (ref "J1") (pin "20") (pinfunction "A4_20") (pintype "bidirectional"))
      (node (ref "U1") (pin "B3") (pinfunction "PA28/BT_CK/RREF_B3") (pintype "bidirectional"))
    )
    (net (code "52") (name "PA30") (class "Default")
      (node (ref "J1") (pin "21") (pinfunction "A3_21") (pintype "bidirectional"))
      (node (ref "S3") (pin "1") (pinfunction "1_1") (pintype "passive"))
      (node (ref "S3") (pin "2") (pinfunction "2_2") (pintype "passive"))
      (node (ref "U1") (pin "B1") (pinfunction "PA30/HS_PWM7_B1") (pintype "bidirectional"))
    )
    (net (code "53") (name "PB1{slash}LP_UART_TXD{slash}A2") (class "Default")
      (node (ref "J1") (pin "14") (pinfunction "TX_14") (pintype "bidirectional"))
      (node (ref "U1") (pin "D8") (pinfunction "PB1/LP_UART_TXD/ADC_D8") (pintype "bidirectional"))
    )
    (net (code "54") (name "PB2{slash}LP_UART_RXD{slash}A1") (class "Default")
      (node (ref "J1") (pin "15") (pinfunction "RX_15") (pintype "bidirectional"))
      (node (ref "U1") (pin "E8") (pinfunction "PB2/LP_UART_RXD/PCM_CLK/ADC_E8") (pintype "bidirectional"))
    )
    (net (code "55") (name "PB3{slash}SWD_CLK{slash}A0") (class "Default")
      (node (ref "J1") (pin "24") (pinfunction "A0_24") (pintype "bidirectional"))
      (node (ref "J6") (pin "4") (pinfunction "SWDCLK_4") (pintype "bidirectional"))
      (node (ref "U1") (pin "J2") (pinfunction "PB3/SWD_CLK/ADC_J2") (pintype "bidirectional"))
    )
    (net (code "56") (name "PB18{slash}SPI0_PICO") (class "Default")
      (node (ref "J1") (pin "17") (pinfunction "PICO_17") (pintype "bidirectional"))
      (node (ref "J4") (pin "3") (pinfunction "CMD/SDI_3") (pintype "bidirectional"))
      (node (ref "U1") (pin "G9") (pinfunction "PB18/SPI0_PICO_G9") (pintype "bidirectional"))
    )
    (net (code "57") (name "PB19{slash}SPI0_POCI") (class "Default")
      (node (ref "J1") (pin "16") (pinfunction "POCI_16") (pintype "bidirectional"))
      (node (ref "J4") (pin "7") (pinfunction "DAT0/SDO_7") (pintype "bidirectional"))
      (node (ref "U1") (pin "G8") (pinfunction "PB19/SPI0_POCI/I2S_TX0_G8") (pintype "bidirectional"))
    )
    (net (code "58") (name "PB20{slash}SPI0_CLK") (class "Default")
      (node (ref "J1") (pin "18") (pinfunction "SCK_18") (pintype "bidirectional"))
      (node (ref "J4") (pin "5") (pinfunction "CLK/SCK_5") (pintype "bidirectional"))
      (node (ref "U1") (pin "F9") (pinfunction "PB20/SPI0_CLK/I2S_CLK_F9") (pintype "bidirectional"))
    )
    (net (code "59") (name "PB21{slash}SPI0_CS") (class "Default")
      (node (ref "J1") (pin "19") (pinfunction "A5_19") (pintype "bidirectional"))
      (node (ref "J4") (pin "2") (pinfunction "DAT3/~{CS}_2") (pintype "bidirectional"))
      (node (ref "R16") (pin "2") (pinfunction "2_2") (pintype "passive"))
      (node (ref "U1") (pin "F8") (pinfunction "PB21/SPI0_CS/I2S_WS/QDEC_IDX_F8") (pintype "bidirectional"))
    )
    (net (code "60") (name "PB22") (class "Default")
      (node (ref "J1") (pin "8") (pinfunction "GPIO1_8") (pintype "bidirectional"))
      (node (ref "JP2") (pin "1") (pinfunction "1_1") (pintype "passive"))
      (node (ref "U1") (pin "E9") (pinfunction "PB22/I2S_SD_RX/QDEC_PHB_E9") (pintype "bidirectional"))
    )
    (net (code "61") (name "PB23{slash}SDPC") (class "Default")
      (node (ref "J1") (pin "7") (pinfunction "GPIO2_7") (pintype "bidirectional"))
      (node (ref "SDPC") (pin "1") (pinfunction "1_1") (pintype "passive"))
      (node (ref "U1") (pin "C8") (pinfunction "PB23/I2S_MCLK/QDEC_PHA_C8") (pintype "bidirectional"))
    )
    (net (code "62") (name "RTS") (class "Default")
      (node (ref "Q2") (pin "4") (pinfunction "E_4") (pintype "passive"))
      (node (ref "R18") (pin "1") (pinfunction "1_1") (pintype "passive"))
      (node (ref "U6") (pin "19") (pinfunction "RTS_19") (pintype "bidirectional"))
    )
    (net (code "63") (name "VIN") (class "Default")
      (node (ref "C7") (pin "1") (pinfunction "1_1") (pintype "passive"))
      (node (ref "MEAS") (pin "2") (pinfunction "2_2") (pintype "passive"))
      (node (ref "MEAS") (pin "4") (pinfunction "2_4") (pintype "passive"))
      (node (ref "R8") (pin "1") (pinfunction "1_1") (pintype "passive"))
      (node (ref "U3") (pin "1") (pinfunction "IN_1") (pintype "input"))
    )
    (net (code "64") (name "V_BATT") (class "Default")
      (node (ref "C15") (pin "1") (pinfunction "1_1") (pintype "passive"))
      (node (ref "C6") (pin "1") (pinfunction "1_1") (pintype "passive"))
      (node (ref "J1") (pin "12") (pinfunction "V_BATT_12") (pintype "bidirectional"))
      (node (ref "J2") (pin "2") (pinfunction "1_2") (pintype "passive"))
      (node (ref "Q1") (pin "3") (pinfunction "D_3") (pintype "bidirectional"))
      (node (ref "U4") (pin "3") (pinfunction "VBAT_3") (pintype "power_in"))
      (node (ref "U5") (pin "2") (pinfunction "CELL_2") (pintype "input"))
      (node (ref "U5") (pin "3") (pinfunction "VDD_3") (pintype "bidirectional"))
    )
    (net (code "65") (name "V_USB") (class "Default")
      (node (ref "C19") (pin "1") (pinfunction "1_1") (pintype "passive"))
      (node (ref "D2") (pin "A") (pinfunction "A_A") (pintype "passive"))
      (node (ref "D6") (pin "5") (pinfunction "5_5") (pintype "power_in"))
      (node (ref "J1") (pin "10") (pinfunction "V_USB_10") (pintype "bidirectional"))
      (node (ref "J5") (pin "VBUS1") (pinfunction "VBUS_VBUS1") (pintype "bidirectional"))
      (node (ref "J5") (pin "VBUS2") (pinfunction "VBUS_VBUS2") (pintype "bidirectional"))
      (node (ref "R10") (pin "1") (pinfunction "1_1") (pintype "passive"))
      (node (ref "R23") (pin "1") (pinfunction "1_1") (pintype "passive"))
      (node (ref "R3") (pin "1") (pinfunction "1_1") (pintype "passive"))
      (node (ref "R5") (pin "2") (pinfunction "2_2") (pintype "passive"))
      (node (ref "R7") (pin "2") (pinfunction "2_2") (pintype "passive"))
      (node (ref "U4") (pin "4") (pinfunction "VIN_4") (pintype "power_in"))
    )
    (net (code "66") (name "WS2812-DO") (class "Default")
      (node (ref "D5") (pin "DO") (pinfunction "DO_DO") (pintype "bidirectional"))
      (node (ref "J1") (pin "9") (pinfunction "GPIO0_9") (pintype "bidirectional"))
    )
    (net (code "67") (name "unconnected-(J1-AREF{slash}NC-Pad26)") (class "Default")
      (node (ref "J1") (pin "26") (pinfunction "AREF/NC_26") (pintype "bidirectional"))
    )
    (net (code "68") (name "unconnected-(J4-DAT1-Pad8)") (class "Default")
      (node (ref "J4") (pin "8") (pinfunction "DAT1_8") (pintype "bidirectional"))
    )
    (net (code "69") (name "unconnected-(J4-DAT2-Pad1)") (class "Default")
      (node (ref "J4") (pin "1") (pinfunction "DAT2_1") (pintype "bidirectional"))
    )
    (net (code "70") (name "unconnected-(J4-DET-Pad9)") (class "Default")
      (node (ref "J4") (pin "9") (pinfunction "DET_9") (pintype "bidirectional"))
    )
    (net (code "71") (name "unconnected-(J6-SWO-Pad6)") (class "Default")
      (node (ref "J6") (pin "6") (pinfunction "SWO_6") (pintype "bidirectional"))
    )
    (net (code "72") (name "unconnected-(U5-~{ALRT}-Pad5)") (class "Default")
      (node (ref "U5") (pin "5") (pinfunction "~{ALRT}_5") (pintype "bidirectional"))
    )
    (net (code "73") (name "unconnected-(U6-CTS-Pad18)") (class "Default")
      (node (ref "U6") (pin "18") (pinfunction "CTS_18") (pintype "bidirectional"))
    )
    (net (code "74") (name "unconnected-(U6-DCD-Pad24)") (class "Default")
      (node (ref "U6") (pin "24") (pinfunction "DCD_24") (pintype "bidirectional"))
    )
    (net (code "75") (name "unconnected-(U6-DSR-Pad22)") (class "Default")
      (node (ref "U6") (pin "22") (pinfunction "DSR_22") (pintype "bidirectional"))
    )
    (net (code "76") (name "unconnected-(U6-GPIO0{slash}TXT-Pad14)") (class "Default")
      (node (ref "U6") (pin "14") (pinfunction "GPIO0/TXT_14") (pintype "bidirectional"))
    )
    (net (code "77") (name "unconnected-(U6-GPIO1{slash}RXT-Pad13)") (class "Default")
      (node (ref "U6") (pin "13") (pinfunction "GPIO1/RXT_13") (pintype "bidirectional"))
    )
    (net (code "78") (name "unconnected-(U6-GPIO2{slash}RS485-Pad12)") (class "Default")
      (node (ref "U6") (pin "12") (pinfunction "GPIO2/RS485_12") (pintype "bidirectional"))
    )
    (net (code "79") (name "unconnected-(U6-GPIO3{slash}WAKEUP-Pad11)") (class "Default")
      (node (ref "U6") (pin "11") (pinfunction "GPIO3/WAKEUP_11") (pintype "bidirectional"))
    )
    (net (code "80") (name "unconnected-(U6-SUSPEND-Pad17)") (class "Default")
      (node (ref "U6") (pin "17") (pinfunction "SUSPEND_17") (pintype "bidirectional"))
    )
    (net (code "81") (name "unconnected-(U6-SUSPENDB-Pad15)") (class "Default")
      (node (ref "U6") (pin "15") (pinfunction "SUSPENDB_15") (pintype "bidirectional"))
    )
    (net (code "82") (name "unconnected-(U6-~{RI}{slash}CLK-Pad1)") (class "Default")
      (node (ref "U6") (pin "1") (pinfunction "~{RI}/CLK_1") (pintype "bidirectional"))
    )
  )
)
